# PiHome_Smart_Home_Gateway_v08_HT7833.net
KiCad netlist of a schematic drawn in EAGLE
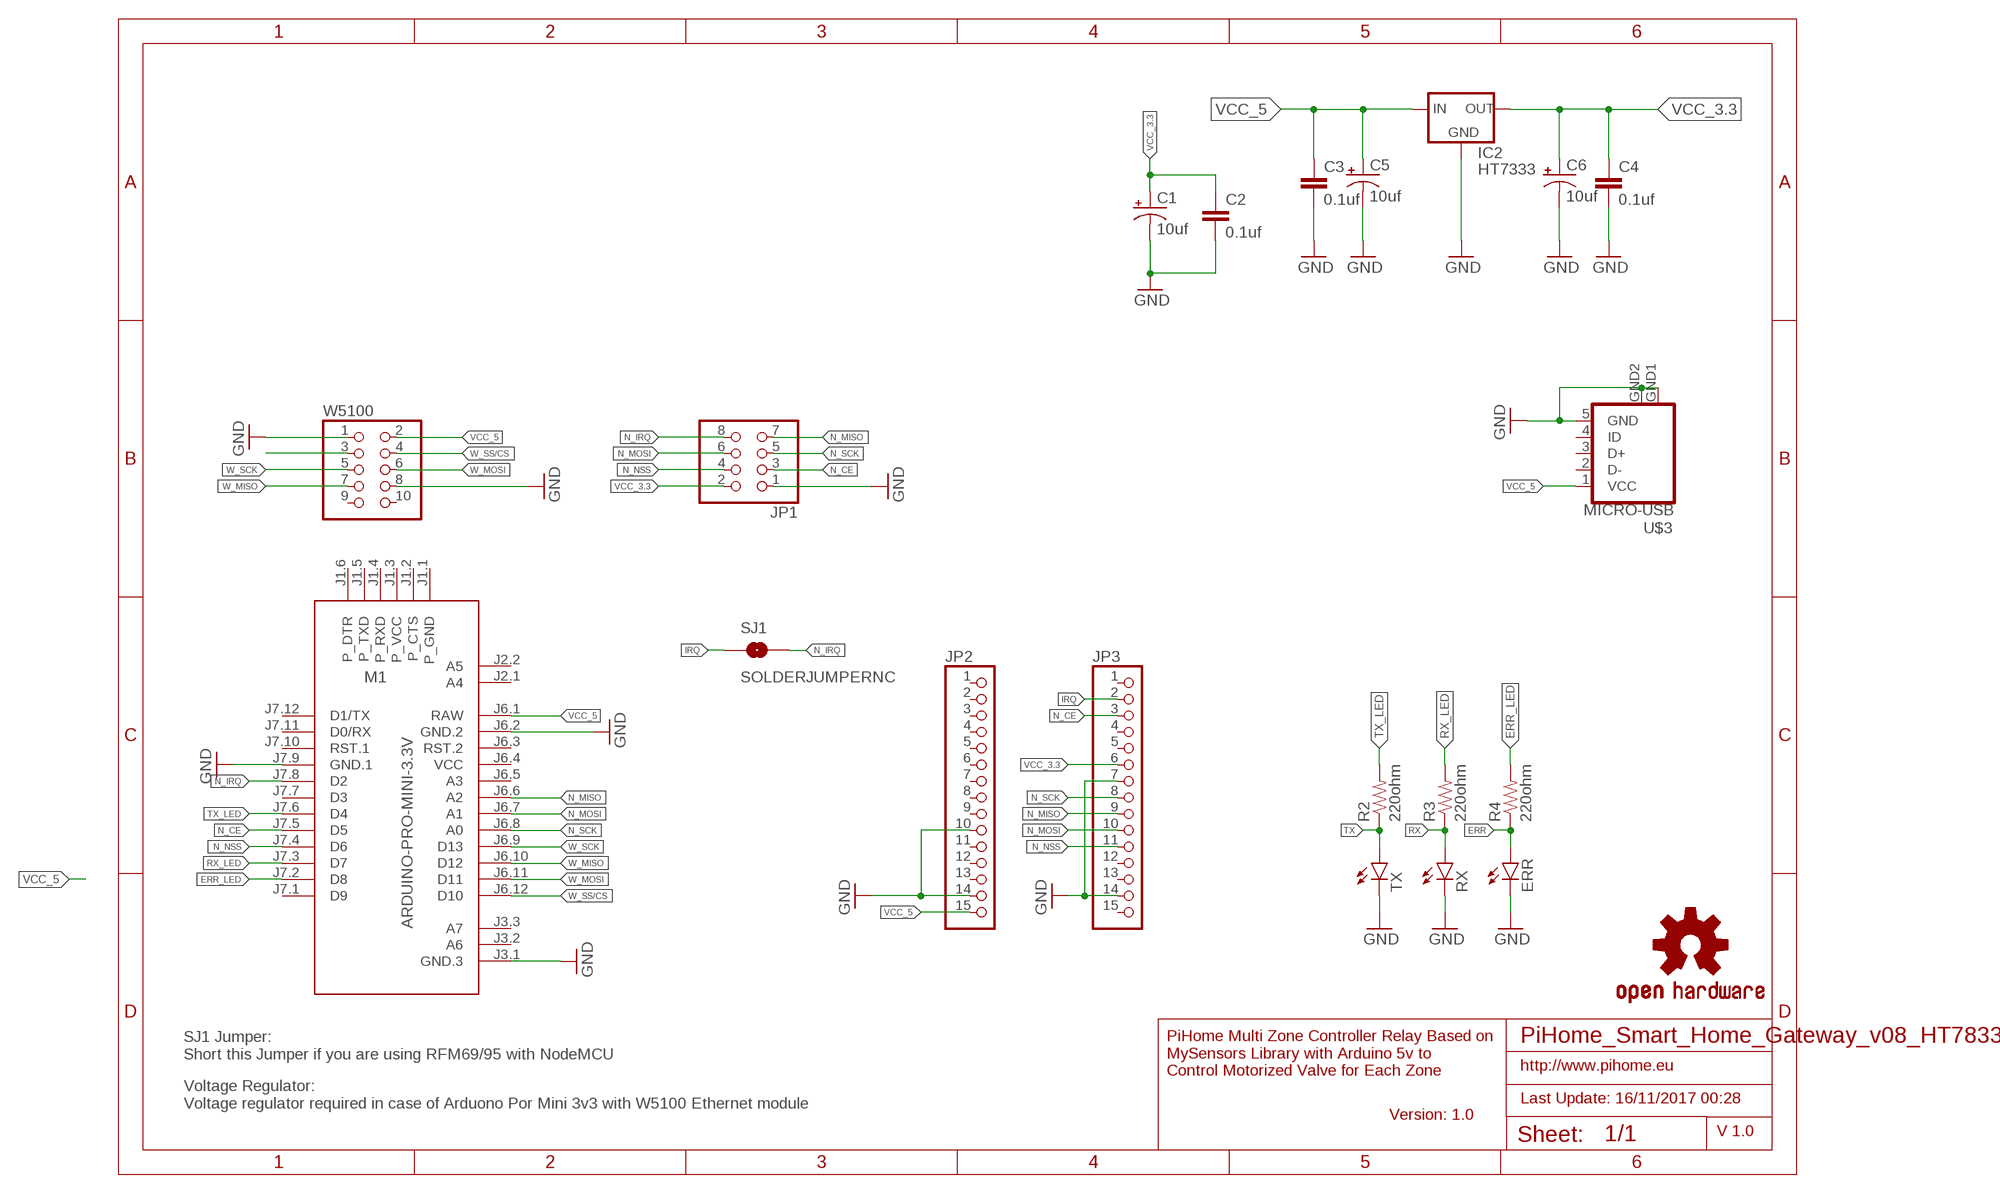
[diagram p0: schematic, sheet 1]

(export (version "E")
  (design (tool "Eeschema 10.0.6"))
  (components
    (comp (ref "C1")
      (value "10uf")
      (footprint "eagle-import:CPOL-RADIAL-10UF-25V-KIT")
      (libsource (lib "eagle-import") (part "10UF-25V-20%(PTH)KIT"))
    )
    (comp (ref "C2")
      (value "0.1uf")
      (footprint "eagle-import:CAP-PTH-SMALL-KIT")
      (libsource (lib "eagle-import") (part "0.1UF-50V-20%(PTH)KIT-EZ"))
    )
    (comp (ref "C3")
      (value "0.1uf")
      (footprint "eagle-import:CAP-PTH-SMALL-KIT")
      (libsource (lib "eagle-import") (part "0.1UF-50V-20%(PTH)KIT-EZ"))
    )
    (comp (ref "C4")
      (value "0.1uf")
      (footprint "eagle-import:CAP-PTH-SMALL-KIT")
      (libsource (lib "eagle-import") (part "0.1UF-50V-20%(PTH)KIT-EZ"))
    )
    (comp (ref "C5")
      (value "10uf")
      (footprint "eagle-import:CPOL-RADIAL-10UF-25V-KIT")
      (libsource (lib "eagle-import") (part "10UF-25V-20%(PTH)KIT"))
    )
    (comp (ref "C6")
      (value "10uf")
      (footprint "eagle-import:CPOL-RADIAL-10UF-25V-KIT")
      (libsource (lib "eagle-import") (part "10UF-25V-20%(PTH)KIT"))
    )
    (comp (ref "ERR")
      (value "LED3MM")
      (footprint "eagle-import:LED3MM")
      (libsource (lib "eagle-import") (part "LED3MM"))
    )
    (comp (ref "IC2")
      (value "HT7333")
      (footprint "eagle-import:SOT-89")
      (libsource (lib "eagle-import") (part "HT7333"))
    )
    (comp (ref "JP1")
      (value "PINHD-2X4")
      (footprint "eagle-import:2X04")
      (libsource (lib "eagle-import") (part "PINHD-2X4"))
    )
    (comp (ref "JP2")
      (value "PINHD-1X15-CB")
      (footprint "eagle-import:1X15-CB")
      (libsource (lib "eagle-import") (part "PINHD-1X15-CB"))
    )
    (comp (ref "JP3")
      (value "PINHD-1X15-CB")
      (footprint "eagle-import:1X15-CB")
      (libsource (lib "eagle-import") (part "PINHD-1X15-CB"))
    )
    (comp (ref "LOGO1")
      (value "OSHW-LOGOMINI")
      (footprint "eagle-import:OSHW-LOGO-MINI")
      (libsource (lib "eagle-import") (part "OSHW-LOGOMINI"))
    )
    (comp (ref "M1")
      (value "ARDUINO-PRO-MINI-3.3V")
      (footprint "eagle-import:ARDUINO-PRO-MINI")
      (libsource (lib "eagle-import") (part "ARDUINO-PRO-MINI-3.3V"))
    )
    (comp (ref "R2")
      (value "220ohm")
      (footprint "eagle-import:AXIAL-0.3")
      (libsource (lib "eagle-import") (part "RESISTORAXIAL-0.3"))
    )
    (comp (ref "R3")
      (value "220ohm")
      (footprint "eagle-import:AXIAL-0.3")
      (libsource (lib "eagle-import") (part "RESISTORAXIAL-0.3"))
    )
    (comp (ref "R4")
      (value "220ohm")
      (footprint "eagle-import:AXIAL-0.3")
      (libsource (lib "eagle-import") (part "RESISTORAXIAL-0.3"))
    )
    (comp (ref "RX")
      (value "LED3MM")
      (footprint "eagle-import:LED3MM")
      (libsource (lib "eagle-import") (part "LED3MM"))
    )
    (comp (ref "SJ1")
      (value "SOLDERJUMPERNC")
      (footprint "eagle-import:SJ_2S")
      (libsource (lib "eagle-import") (part "SOLDERJUMPERNC"))
    )
    (comp (ref "TX")
      (value "LED3MM")
      (footprint "eagle-import:LED3MM")
      (libsource (lib "eagle-import") (part "LED3MM"))
    )
    (comp (ref "U$3")
      (value "MICRO-USB")
      (footprint "eagle-import:MICRO-USB")
      (libsource (lib "eagle-import") (part "MICRO-USB"))
    )
    (comp (ref "W5100")
      (value "PINHD-2X5")
      (footprint "eagle-import:2X05")
      (libsource (lib "eagle-import") (part "PINHD-2X5"))
    )
  )
  (nets
    (net (code "1") (name "/VCC") (class "Default")
      (node (ref "M1") (pin "J6.4") (pinfunction "VCC_J6.4") (pintype "power_in"))
    )
    (net (code "2") (name "ERR") (class "Default")
      (node (ref "ERR") (pin "A") (pinfunction "A_A") (pintype "passive"))
      (node (ref "R4") (pin "P$1") (pinfunction "1_P$1") (pintype "passive"))
    )
    (net (code "3") (name "ERR_LED") (class "Default")
      (node (ref "M1") (pin "J7.2") (pinfunction "D8_J7.2") (pintype "bidirectional"))
      (node (ref "R4") (pin "P$2") (pinfunction "2_P$2") (pintype "passive"))
    )
    (net (code "4") (name "GND") (class "Default")
      (node (ref "C1") (pin "2") (pinfunction "-_2") (pintype "passive"))
      (node (ref "C2") (pin "2") (pinfunction "2_2") (pintype "passive"))
      (node (ref "C3") (pin "2") (pinfunction "2_2") (pintype "passive"))
      (node (ref "C4") (pin "2") (pinfunction "2_2") (pintype "passive"))
      (node (ref "C5") (pin "2") (pinfunction "-_2") (pintype "passive"))
      (node (ref "C6") (pin "2") (pinfunction "-_2") (pintype "passive"))
      (node (ref "ERR") (pin "K") (pinfunction "C_K") (pintype "passive"))
      (node (ref "IC2") (pin "2") (pinfunction "GND_2") (pintype "input"))
      (node (ref "JP1") (pin "1") (pinfunction "1_1") (pintype "passive"))
      (node (ref "JP2") (pin "10") (pinfunction "10_10") (pintype "passive"))
      (node (ref "JP2") (pin "14") (pinfunction "14_14") (pintype "passive"))
      (node (ref "JP3") (pin "14") (pinfunction "14_14") (pintype "passive"))
      (node (ref "JP3") (pin "7") (pinfunction "7_7") (pintype "passive"))
      (node (ref "M1") (pin "J3.1") (pinfunction "GND.3_J3.1") (pintype "bidirectional"))
      (node (ref "M1") (pin "J6.2") (pinfunction "GND.2_J6.2") (pintype "power_in"))
      (node (ref "M1") (pin "J7.9") (pinfunction "GND.1_J7.9") (pintype "power_in"))
      (node (ref "RX") (pin "K") (pinfunction "C_K") (pintype "passive"))
      (node (ref "TX") (pin "K") (pinfunction "C_K") (pintype "passive"))
      (node (ref "U$3") (pin "5") (pinfunction "GND_5") (pintype "power_in"))
      (node (ref "U$3") (pin "GND1") (pinfunction "GND_GND1") (pintype "power_in"))
      (node (ref "U$3") (pin "GND2") (pinfunction "GND_GND2") (pintype "power_in"))
      (node (ref "W5100") (pin "1") (pinfunction "1_1") (pintype "passive"))
      (node (ref "W5100") (pin "8") (pinfunction "8_8") (pintype "passive"))
    )
    (net (code "5") (name "IRQ") (class "Default")
      (node (ref "JP3") (pin "2") (pinfunction "2_2") (pintype "passive"))
      (node (ref "SJ1") (pin "1") (pinfunction "1_1") (pintype "passive"))
    )
    (net (code "6") (name "N_CE") (class "Default")
      (node (ref "JP1") (pin "3") (pinfunction "3_3") (pintype "passive"))
      (node (ref "JP3") (pin "3") (pinfunction "3_3") (pintype "passive"))
      (node (ref "M1") (pin "J7.5") (pinfunction "D5_J7.5") (pintype "bidirectional"))
    )
    (net (code "7") (name "N_IRQ") (class "Default")
      (node (ref "JP1") (pin "8") (pinfunction "8_8") (pintype "passive"))
      (node (ref "M1") (pin "J7.8") (pinfunction "D2_J7.8") (pintype "bidirectional"))
      (node (ref "SJ1") (pin "2") (pinfunction "2_2") (pintype "passive"))
    )
    (net (code "8") (name "N_MISO") (class "Default")
      (node (ref "JP1") (pin "7") (pinfunction "7_7") (pintype "passive"))
      (node (ref "JP3") (pin "9") (pinfunction "9_9") (pintype "passive"))
      (node (ref "M1") (pin "J6.6") (pinfunction "A2_J6.6") (pintype "bidirectional"))
    )
    (net (code "9") (name "N_MOSI") (class "Default")
      (node (ref "JP1") (pin "6") (pinfunction "6_6") (pintype "passive"))
      (node (ref "JP3") (pin "10") (pinfunction "10_10") (pintype "passive"))
      (node (ref "M1") (pin "J6.7") (pinfunction "A1_J6.7") (pintype "bidirectional"))
    )
    (net (code "10") (name "N_NSS") (class "Default")
      (node (ref "JP1") (pin "4") (pinfunction "4_4") (pintype "passive"))
      (node (ref "JP3") (pin "11") (pinfunction "11_11") (pintype "passive"))
      (node (ref "M1") (pin "J7.4") (pinfunction "D6_J7.4") (pintype "bidirectional"))
    )
    (net (code "11") (name "N_SCK") (class "Default")
      (node (ref "JP1") (pin "5") (pinfunction "5_5") (pintype "passive"))
      (node (ref "JP3") (pin "8") (pinfunction "8_8") (pintype "passive"))
      (node (ref "M1") (pin "J6.8") (pinfunction "A0_J6.8") (pintype "bidirectional"))
    )
    (net (code "12") (name "RX") (class "Default")
      (node (ref "R3") (pin "P$1") (pinfunction "1_P$1") (pintype "passive"))
      (node (ref "RX") (pin "A") (pinfunction "A_A") (pintype "passive"))
    )
    (net (code "13") (name "RX_LED") (class "Default")
      (node (ref "M1") (pin "J7.3") (pinfunction "D7_J7.3") (pintype "bidirectional"))
      (node (ref "R3") (pin "P$2") (pinfunction "2_P$2") (pintype "passive"))
    )
    (net (code "14") (name "TX") (class "Default")
      (node (ref "R2") (pin "P$1") (pinfunction "1_P$1") (pintype "passive"))
      (node (ref "TX") (pin "A") (pinfunction "A_A") (pintype "passive"))
    )
    (net (code "15") (name "TX_LED") (class "Default")
      (node (ref "M1") (pin "J7.6") (pinfunction "D4_J7.6") (pintype "bidirectional"))
      (node (ref "R2") (pin "P$2") (pinfunction "2_P$2") (pintype "passive"))
    )
    (net (code "16") (name "VCC_3.3") (class "Default")
      (node (ref "C1") (pin "1") (pinfunction "+_1") (pintype "passive"))
      (node (ref "C2") (pin "1") (pinfunction "1_1") (pintype "passive"))
      (node (ref "C4") (pin "1") (pinfunction "1_1") (pintype "passive"))
      (node (ref "C6") (pin "1") (pinfunction "+_1") (pintype "passive"))
      (node (ref "IC2") (pin "1") (pinfunction "OUT_1") (pintype "passive"))
      (node (ref "JP1") (pin "2") (pinfunction "2_2") (pintype "passive"))
      (node (ref "JP3") (pin "6") (pinfunction "6_6") (pintype "passive"))
    )
    (net (code "17") (name "VCC_5") (class "Default")
      (node (ref "C3") (pin "1") (pinfunction "1_1") (pintype "passive"))
      (node (ref "C5") (pin "1") (pinfunction "+_1") (pintype "passive"))
      (node (ref "IC2") (pin "3") (pinfunction "IN_3") (pintype "input"))
      (node (ref "IC2") (pin "4") (pinfunction "IN_4") (pintype "input"))
      (node (ref "JP2") (pin "15") (pinfunction "15_15") (pintype "passive"))
      (node (ref "M1") (pin "J6.1") (pinfunction "RAW_J6.1") (pintype "power_in"))
      (node (ref "U$3") (pin "1") (pinfunction "VCC_1") (pintype "power_in"))
      (node (ref "W5100") (pin "2") (pinfunction "2_2") (pintype "passive"))
    )
    (net (code "18") (name "W_MISO") (class "Default")
      (node (ref "M1") (pin "J6.10") (pinfunction "D12_J6.10") (pintype "bidirectional"))
      (node (ref "W5100") (pin "7") (pinfunction "7_7") (pintype "passive"))
    )
    (net (code "19") (name "W_MOSI") (class "Default")
      (node (ref "M1") (pin "J6.11") (pinfunction "D11_J6.11") (pintype "bidirectional"))
      (node (ref "W5100") (pin "6") (pinfunction "6_6") (pintype "passive"))
    )
    (net (code "20") (name "W_SCK") (class "Default")
      (node (ref "M1") (pin "J6.9") (pinfunction "D13_J6.9") (pintype "bidirectional"))
      (node (ref "W5100") (pin "5") (pinfunction "5_5") (pintype "passive"))
    )
    (net (code "21") (name "W_SS{slash}CS") (class "Default")
      (node (ref "M1") (pin "J6.12") (pinfunction "D10_J6.12") (pintype "bidirectional"))
      (node (ref "W5100") (pin "4") (pinfunction "4_4") (pintype "passive"))
    )
    (net (code "22") (name "unconnected-(JP2-Pad1)") (class "Default")
      (node (ref "JP2") (pin "1") (pinfunction "1_1") (pintype "passive"))
    )
    (net (code "23") (name "unconnected-(JP2-Pad2)") (class "Default")
      (node (ref "JP2") (pin "2") (pinfunction "2_2") (pintype "passive"))
    )
    (net (code "24") (name "unconnected-(JP2-Pad3)") (class "Default")
      (node (ref "JP2") (pin "3") (pinfunction "3_3") (pintype "passive"))
    )
    (net (code "25") (name "unconnected-(JP2-Pad4)") (class "Default")
      (node (ref "JP2") (pin "4") (pinfunction "4_4") (pintype "passive"))
    )
    (net (code "26") (name "unconnected-(JP2-Pad5)") (class "Default")
      (node (ref "JP2") (pin "5") (pinfunction "5_5") (pintype "passive"))
    )
    (net (code "27") (name "unconnected-(JP2-Pad6)") (class "Default")
      (node (ref "JP2") (pin "6") (pinfunction "6_6") (pintype "passive"))
    )
    (net (code "28") (name "unconnected-(JP2-Pad7)") (class "Default")
      (node (ref "JP2") (pin "7") (pinfunction "7_7") (pintype "passive"))
    )
    (net (code "29") (name "unconnected-(JP2-Pad8)") (class "Default")
      (node (ref "JP2") (pin "8") (pinfunction "8_8") (pintype "passive"))
    )
    (net (code "30") (name "unconnected-(JP2-Pad9)") (class "Default")
      (node (ref "JP2") (pin "9") (pinfunction "9_9") (pintype "passive"))
    )
    (net (code "31") (name "unconnected-(JP2-Pad11)") (class "Default")
      (node (ref "JP2") (pin "11") (pinfunction "11_11") (pintype "passive"))
    )
    (net (code "32") (name "unconnected-(JP2-Pad12)") (class "Default")
      (node (ref "JP2") (pin "12") (pinfunction "12_12") (pintype "passive"))
    )
    (net (code "33") (name "unconnected-(JP2-Pad13)") (class "Default")
      (node (ref "JP2") (pin "13") (pinfunction "13_13") (pintype "passive"))
    )
    (net (code "34") (name "unconnected-(JP3-Pad1)") (class "Default")
      (node (ref "JP3") (pin "1") (pinfunction "1_1") (pintype "passive"))
    )
    (net (code "35") (name "unconnected-(JP3-Pad4)") (class "Default")
      (node (ref "JP3") (pin "4") (pinfunction "4_4") (pintype "passive"))
    )
    (net (code "36") (name "unconnected-(JP3-Pad5)") (class "Default")
      (node (ref "JP3") (pin "5") (pinfunction "5_5") (pintype "passive"))
    )
    (net (code "37") (name "unconnected-(JP3-Pad12)") (class "Default")
      (node (ref "JP3") (pin "12") (pinfunction "12_12") (pintype "passive"))
    )
    (net (code "38") (name "unconnected-(JP3-Pad13)") (class "Default")
      (node (ref "JP3") (pin "13") (pinfunction "13_13") (pintype "passive"))
    )
    (net (code "39") (name "unconnected-(JP3-Pad15)") (class "Default")
      (node (ref "JP3") (pin "15") (pinfunction "15_15") (pintype "passive"))
    )
    (net (code "40") (name "unconnected-(M1-A3-PadJ6.5)") (class "Default")
      (node (ref "M1") (pin "J6.5") (pinfunction "A3_J6.5") (pintype "bidirectional"))
    )
    (net (code "41") (name "unconnected-(M1-A4-PadJ2.1)") (class "Default")
      (node (ref "M1") (pin "J2.1") (pinfunction "A4_J2.1") (pintype "bidirectional"))
    )
    (net (code "42") (name "unconnected-(M1-A5-PadJ2.2)") (class "Default")
      (node (ref "M1") (pin "J2.2") (pinfunction "A5_J2.2") (pintype "bidirectional"))
    )
    (net (code "43") (name "unconnected-(M1-A6-PadJ3.2)") (class "Default")
      (node (ref "M1") (pin "J3.2") (pinfunction "A6_J3.2") (pintype "bidirectional"))
    )
    (net (code "44") (name "unconnected-(M1-A7-PadJ3.3)") (class "Default")
      (node (ref "M1") (pin "J3.3") (pinfunction "A7_J3.3") (pintype "bidirectional"))
    )
    (net (code "45") (name "unconnected-(M1-D0{slash}RX-PadJ7.11)") (class "Default")
      (node (ref "M1") (pin "J7.11") (pinfunction "D0/RX_J7.11") (pintype "bidirectional"))
    )
    (net (code "46") (name "unconnected-(M1-D1{slash}TX-PadJ7.12)") (class "Default")
      (node (ref "M1") (pin "J7.12") (pinfunction "D1/TX_J7.12") (pintype "bidirectional"))
    )
    (net (code "47") (name "unconnected-(M1-D3-PadJ7.7)") (class "Default")
      (node (ref "M1") (pin "J7.7") (pinfunction "D3_J7.7") (pintype "bidirectional"))
    )
    (net (code "48") (name "unconnected-(M1-D9-PadJ7.1)") (class "Default")
      (node (ref "M1") (pin "J7.1") (pinfunction "D9_J7.1") (pintype "bidirectional"))
    )
    (net (code "49") (name "unconnected-(M1-P_CTS-PadJ1.2)") (class "Default")
      (node (ref "M1") (pin "J1.2") (pinfunction "P_CTS_J1.2") (pintype "bidirectional"))
    )
    (net (code "50") (name "unconnected-(M1-P_DTR-PadJ1.6)") (class "Default")
      (node (ref "M1") (pin "J1.6") (pinfunction "P_DTR_J1.6") (pintype "bidirectional"))
    )
    (net (code "51") (name "unconnected-(M1-P_GND-PadJ1.1)") (class "Default")
      (node (ref "M1") (pin "J1.1") (pinfunction "P_GND_J1.1") (pintype "bidirectional"))
    )
    (net (code "52") (name "unconnected-(M1-P_RXD-PadJ1.4)") (class "Default")
      (node (ref "M1") (pin "J1.4") (pinfunction "P_RXD_J1.4") (pintype "bidirectional"))
    )
    (net (code "53") (name "unconnected-(M1-P_TXD-PadJ1.5)") (class "Default")
      (node (ref "M1") (pin "J1.5") (pinfunction "P_TXD_J1.5") (pintype "bidirectional"))
    )
    (net (code "54") (name "unconnected-(M1-P_VCC-PadJ1.3)") (class "Default")
      (node (ref "M1") (pin "J1.3") (pinfunction "P_VCC_J1.3") (pintype "bidirectional"))
    )
    (net (code "55") (name "unconnected-(M1-RST.1-PadJ7.10)") (class "Default")
      (node (ref "M1") (pin "J7.10") (pinfunction "RST.1_J7.10") (pintype "bidirectional"))
    )
    (net (code "56") (name "unconnected-(M1-RST.2-PadJ6.3)") (class "Default")
      (node (ref "M1") (pin "J6.3") (pinfunction "RST.2_J6.3") (pintype "bidirectional"))
    )
    (net (code "57") (name "unconnected-(U$3-D+-Pad3)") (class "Default")
      (node (ref "U$3") (pin "3") (pinfunction "D+_3") (pintype "bidirectional"))
    )
    (net (code "58") (name "unconnected-(U$3-D--Pad2)") (class "Default")
      (node (ref "U$3") (pin "2") (pinfunction "D-_2") (pintype "bidirectional"))
    )
    (net (code "59") (name "unconnected-(U$3-ID-Pad4)") (class "Default")
      (node (ref "U$3") (pin "4") (pinfunction "ID_4") (pintype "bidirectional"))
    )
    (net (code "60") (name "unconnected-(W5100-Pad3)") (class "Default")
      (node (ref "W5100") (pin "3") (pinfunction "3_3") (pintype "passive"))
    )
    (net (code "61") (name "unconnected-(W5100-Pad9)") (class "Default")
      (node (ref "W5100") (pin "9") (pinfunction "9_9") (pintype "passive"))
    )
    (net (code "62") (name "unconnected-(W5100-Pad10)") (class "Default")
      (node (ref "W5100") (pin "10") (pinfunction "10_10") (pintype "passive"))
    )
  )
)
